# COMM_Circuitry.net
KiCad netlist of a schematic drawn in Altium Designer
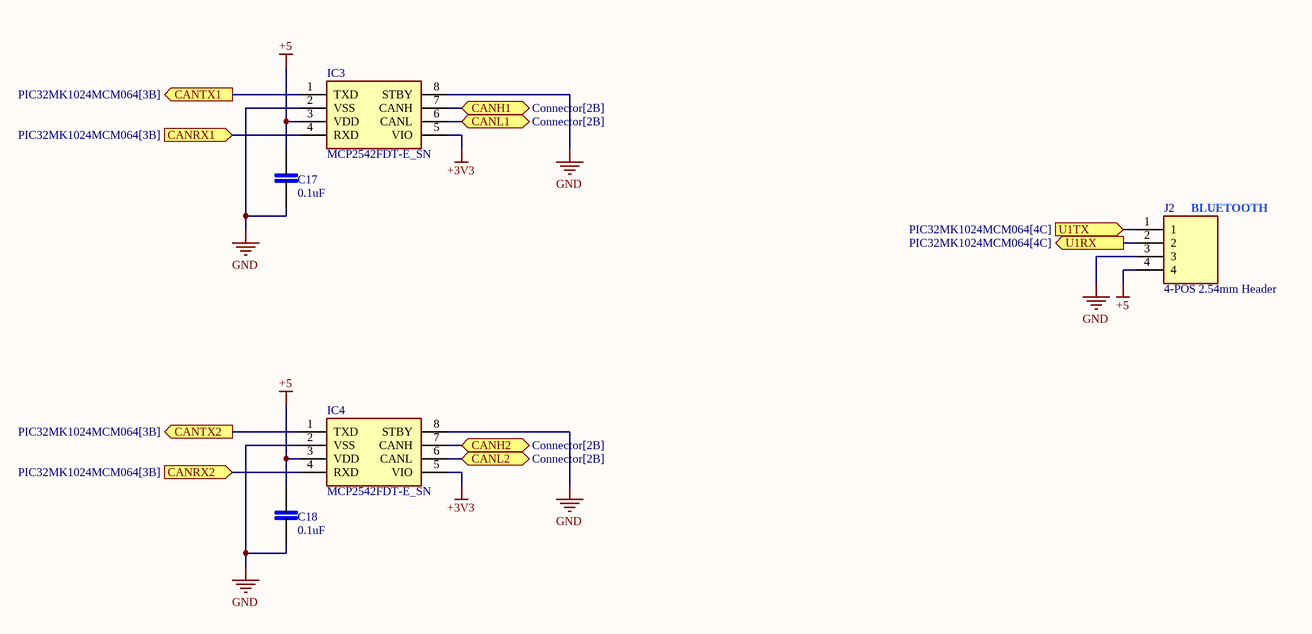
[diagram p0: COMM Circuitry.SchDoc]

(export (version "E")
  (design (tool "Eeschema 10.0.6"))
  (components
    (comp (ref "C17")
      (value "0.1uF")
      (footprint "0805")
      (fields (field (name "MP") "LD051A121KAB2A") (field (name "MF") "AVX"))
      (libsource (lib "Capacitors SMD") (part "0805_Capacitor"))
    )
    (comp (ref "C18")
      (value "0.1uF")
      (footprint "0805")
      (fields (field (name "MP") "LD051A121KAB2A") (field (name "MF") "AVX"))
      (libsource (lib "Capacitors SMD") (part "0805_Capacitor"))
    )
    (comp (ref "IC3")
      (value "MCP2542FDT-E_SN")
      (footprint "Transceiver CAN:MCP2542FDT-E_SN")
      (description "Integrated Circuit")
      (fields
        (field (name "MANUFACTURER_PART_NUMBER") "MCP2542FDT-E/SN")
        (field (name "MOUSER PART NUMBER") "579-MCP2542FDT-E/SN")
      )
      (libsource (lib "Transceiver CAN") (part "MCP2542FDT-E_SN"))
    )
    (comp (ref "IC4")
      (value "MCP2542FDT-E_SN")
      (footprint "Transceiver CAN:MCP2542FDT-E_SN")
      (description "Integrated Circuit")
      (fields
        (field (name "MANUFACTURER_PART_NUMBER") "MCP2542FDT-E/SN")
        (field (name "MOUSER PART NUMBER") "579-MCP2542FDT-E/SN")
      )
      (libsource (lib "Transceiver CAN") (part "MCP2542FDT-E_SN"))
    )
    (comp (ref "J2")
      (value "4-POS 2.54mm Header")
      (footprint "Connectors Through Hole:4-POS 2.54mm Header")
      (fields (field (name "MP") "5-146290-4"))
      (libsource (lib "Connectors Through Hole") (part "4-POS 2.54mm Header"))
    )
  )
  (nets
    (net (code "1") (name "+3V3") (class "Default")
      (node (ref "IC3") (pin "5") (pinfunction "VIO_5") (pintype "passive"))
      (node (ref "IC4") (pin "5") (pinfunction "VIO_5") (pintype "passive"))
    )
    (net (code "2") (name "+5") (class "Default")
      (node (ref "C17") (pin "2") (pinfunction "2_2") (pintype "passive"))
      (node (ref "C18") (pin "2") (pinfunction "2_2") (pintype "passive"))
      (node (ref "IC3") (pin "3") (pinfunction "VDD_3") (pintype "passive"))
      (node (ref "IC4") (pin "3") (pinfunction "VDD_3") (pintype "passive"))
      (node (ref "J2") (pin "4") (pinfunction "4_4") (pintype "passive"))
    )
    (net (code "3") (name "/CANH1") (class "Default")
      (node (ref "IC3") (pin "7") (pinfunction "CANH_7") (pintype "passive"))
    )
    (net (code "4") (name "/CANH2") (class "Default")
      (node (ref "IC4") (pin "7") (pinfunction "CANH_7") (pintype "passive"))
    )
    (net (code "5") (name "/CANL1") (class "Default")
      (node (ref "IC3") (pin "6") (pinfunction "CANL_6") (pintype "passive"))
    )
    (net (code "6") (name "/CANL2") (class "Default")
      (node (ref "IC4") (pin "6") (pinfunction "CANL_6") (pintype "passive"))
    )
    (net (code "7") (name "/CANRX1") (class "Default")
      (node (ref "IC3") (pin "4") (pinfunction "RXD_4") (pintype "passive"))
    )
    (net (code "8") (name "/CANRX2") (class "Default")
      (node (ref "IC4") (pin "4") (pinfunction "RXD_4") (pintype "passive"))
    )
    (net (code "9") (name "/CANTX1") (class "Default")
      (node (ref "IC3") (pin "1") (pinfunction "TXD_1") (pintype "passive"))
    )
    (net (code "10") (name "/CANTX2") (class "Default")
      (node (ref "IC4") (pin "1") (pinfunction "TXD_1") (pintype "passive"))
    )
    (net (code "11") (name "/U1RX") (class "Default")
      (node (ref "J2") (pin "2") (pinfunction "2_2") (pintype "passive"))
    )
    (net (code "12") (name "/U1TX") (class "Default")
      (node (ref "J2") (pin "1") (pinfunction "1_1") (pintype "passive"))
    )
    (net (code "13") (name "GND") (class "Default")
      (node (ref "C17") (pin "1") (pinfunction "1_1") (pintype "passive"))
      (node (ref "C18") (pin "1") (pinfunction "1_1") (pintype "passive"))
      (node (ref "IC3") (pin "2") (pinfunction "VSS_2") (pintype "passive"))
      (node (ref "IC3") (pin "8") (pinfunction "STBY_8") (pintype "passive"))
      (node (ref "IC4") (pin "2") (pinfunction "VSS_2") (pintype "passive"))
      (node (ref "IC4") (pin "8") (pinfunction "STBY_8") (pintype "passive"))
      (node (ref "J2") (pin "3") (pinfunction "3_3") (pintype "passive"))
    )
  )
)
